# SimulatorT2InterfaceRevE.net
KiCad netlist of a schematic drawn in EAGLE
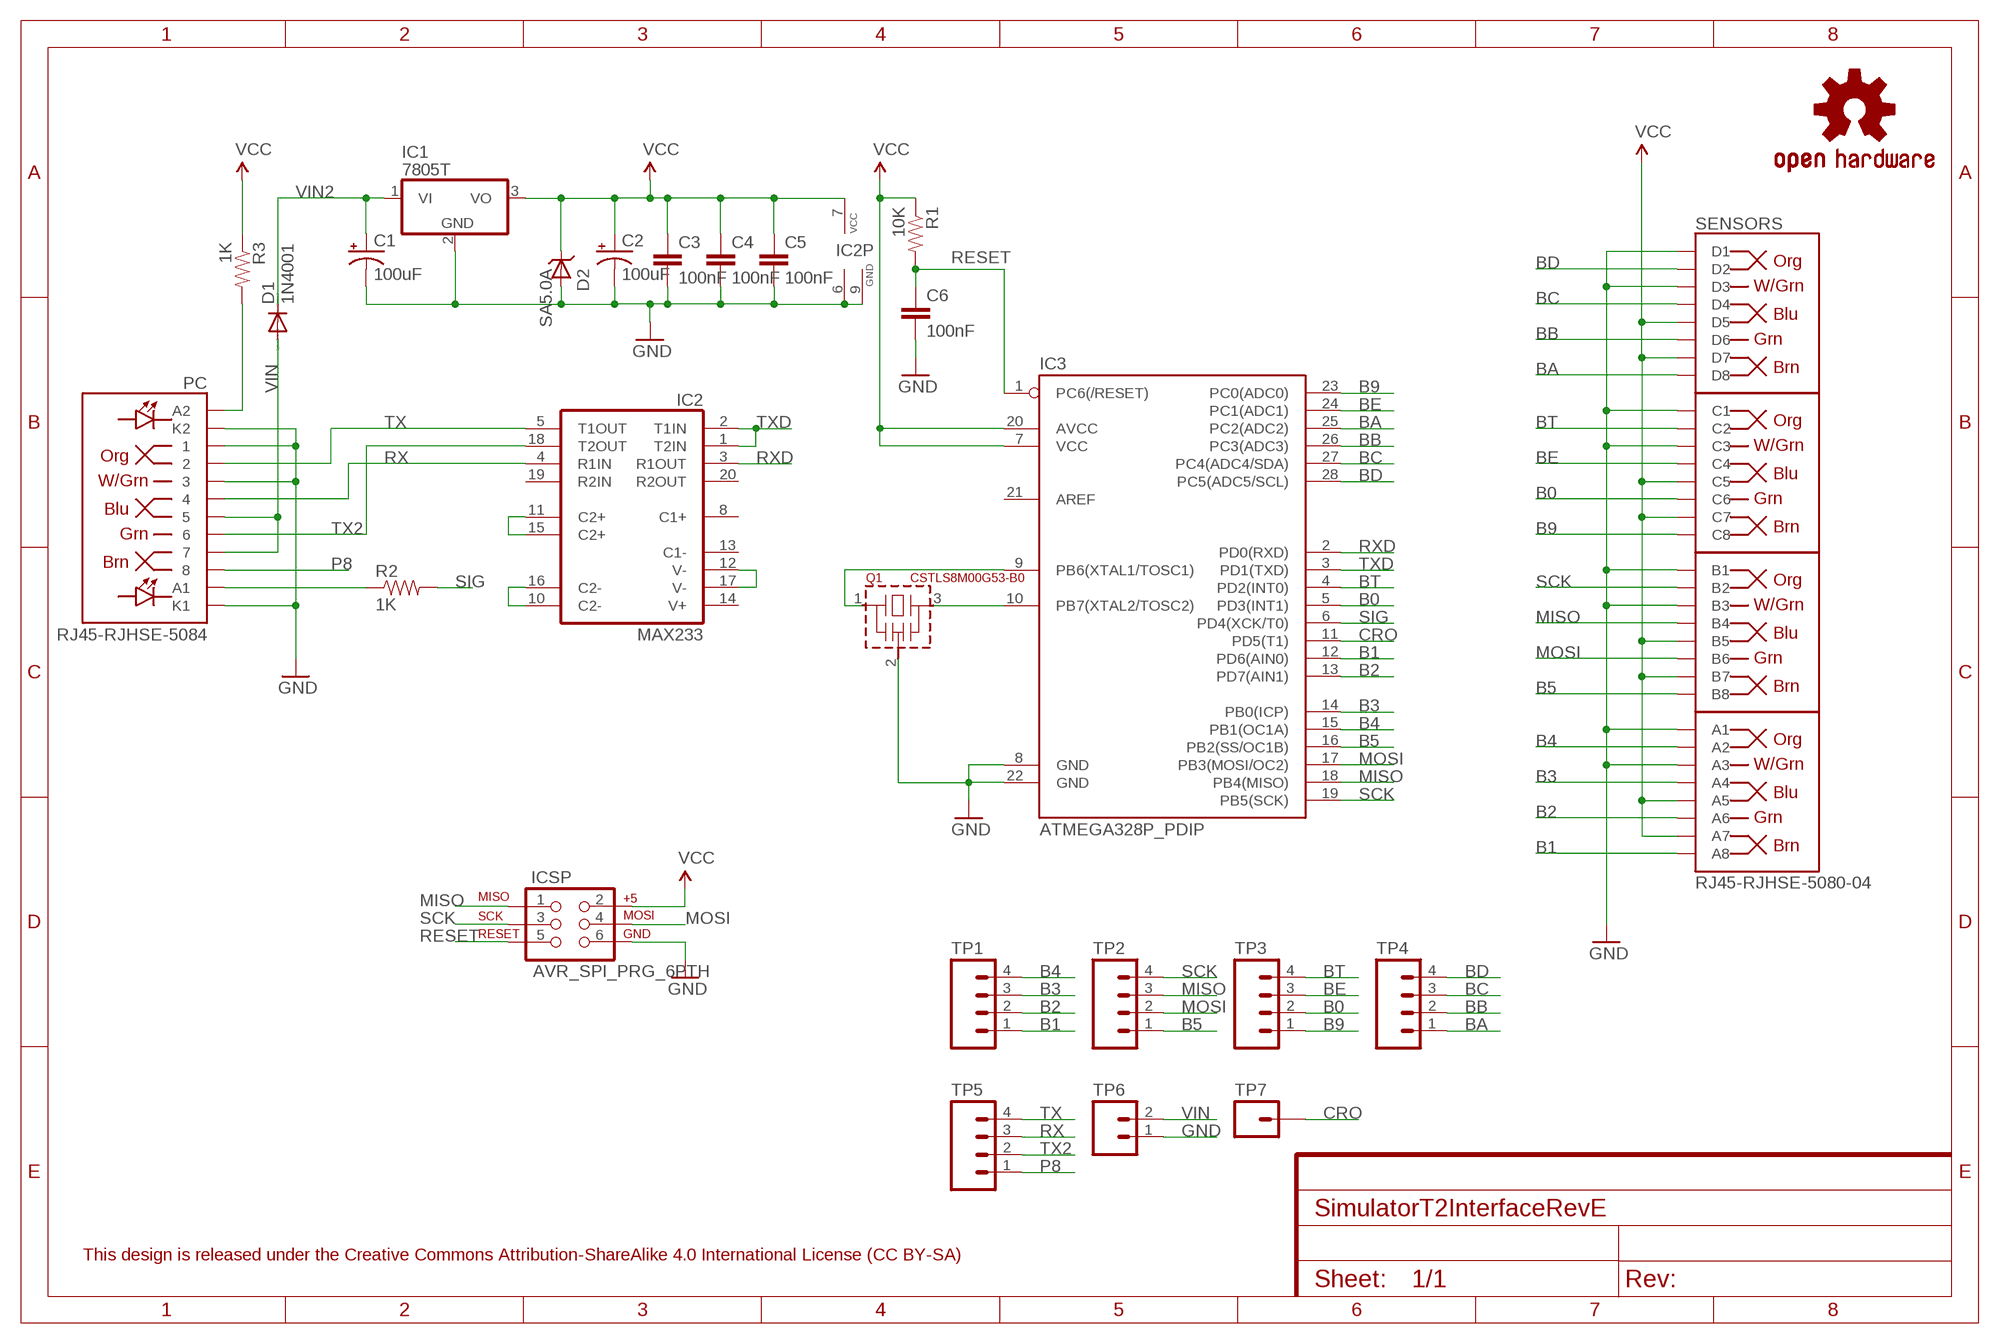
[diagram p0: schematic, sheet 1]

(export (version "E")
  (design (tool "Eeschema 10.0.6"))
  (components
    (comp (ref "C1")
      (value "100uF")
      (footprint "eagle-import:CPOL-RADIAL-100UF-25V")
      (libsource (lib "eagle-import") (part "CAP_POLPTH1"))
    )
    (comp (ref "C2")
      (value "100uF")
      (footprint "eagle-import:CPOL-RADIAL-100UF-25V")
      (libsource (lib "eagle-import") (part "CAP_POLPTH1"))
    )
    (comp (ref "C3")
      (value "100nF")
      (footprint "eagle-import:CAP-PTH-SMALL")
      (libsource (lib "eagle-import") (part "CAPPTH"))
    )
    (comp (ref "C4")
      (value "100nF")
      (footprint "eagle-import:CAP-PTH-SMALL")
      (libsource (lib "eagle-import") (part "CAPPTH"))
    )
    (comp (ref "C5")
      (value "100nF")
      (footprint "eagle-import:CAP-PTH-SMALL")
      (libsource (lib "eagle-import") (part "CAPPTH"))
    )
    (comp (ref "C6")
      (value "100nF")
      (footprint "eagle-import:CAP-PTH-SMALL")
      (libsource (lib "eagle-import") (part "CAPPTH"))
    )
    (comp (ref "D1")
      (value "1N4001")
      (footprint "eagle-import:DO41_DIODE")
      (libsource (lib "eagle-import") (part "1N4001"))
    )
    (comp (ref "D2")
      (value "SA5.0A")
      (footprint "eagle-import:DO41_TVS_UNI")
      (libsource (lib "eagle-import") (part "SA5.0A"))
    )
    (comp (ref "IC1")
      (value "7805T")
      (footprint "eagle-import:TO220H+TSR")
      (libsource (lib "eagle-import") (part "7805T"))
    )
    (comp (ref "IC2")
      (value "MAX233")
      (footprint "eagle-import:DIL20")
      (fields (field (name "MPN") "MAX233ACPP+G36"))
      (libsource (lib "eagle-import") (part "MAX233"))
    )
    (comp (ref "IC3")
      (value "ATMEGA328P_PDIP")
      (footprint "eagle-import:DIL28-3")
      (libsource (lib "eagle-import") (part "ATMEGA328P_PDIP"))
    )
    (comp (ref "ICSP")
      (value "AVR_SPI_PRG_6PTH")
      (footprint "eagle-import:2X3")
      (libsource (lib "eagle-import") (part "AVR_SPI_PRG_6PTH"))
    )
    (comp (ref "LOGO1")
      (value "OSHW-LOGOS")
      (footprint "eagle-import:OSHW-LOGO-S")
      (libsource (lib "eagle-import") (part "OSHW-LOGOS"))
    )
    (comp (ref "PC")
      (value "RJ45-RJHSE-5084")
      (footprint "eagle-import:RJ45-RJHSE-5084")
      (libsource (lib "eagle-import") (part "RJ45-RJHSE-5084"))
    )
    (comp (ref "Q1")
      (value "CSTLS8M00G53-B0")
      (footprint "eagle-import:CSTLS_G9")
      (libsource (lib "eagle-import") (part "murata-resonators_CSTLS_G"))
    )
    (comp (ref "R1")
      (value "10K")
      (footprint "eagle-import:AXIAL-0.4")
      (libsource (lib "eagle-import") (part "RESISTORPTH-1/4W"))
    )
    (comp (ref "R2")
      (value "1K")
      (footprint "eagle-import:AXIAL-0.4")
      (libsource (lib "eagle-import") (part "RESISTORPTH-1/4W"))
    )
    (comp (ref "R3")
      (value "1K")
      (footprint "eagle-import:AXIAL-0.4")
      (libsource (lib "eagle-import") (part "RESISTORPTH-1/4W"))
    )
    (comp (ref "SENSORS")
      (value "RJ45-RJHSE-5080-04")
      (footprint "eagle-import:RJ45-RJHSE-5080-04")
      (libsource (lib "eagle-import") (part "RJ45-RJHSE-5080-04"))
    )
    (comp (ref "TP1")
      (value "M04PTH")
      (footprint "eagle-import:1X04")
      (libsource (lib "eagle-import") (part "M04PTH"))
    )
    (comp (ref "TP2")
      (value "M04PTH")
      (footprint "eagle-import:1X04")
      (libsource (lib "eagle-import") (part "M04PTH"))
    )
    (comp (ref "TP3")
      (value "M04PTH")
      (footprint "eagle-import:1X04")
      (libsource (lib "eagle-import") (part "M04PTH"))
    )
    (comp (ref "TP4")
      (value "M04PTH")
      (footprint "eagle-import:1X04")
      (libsource (lib "eagle-import") (part "M04PTH"))
    )
    (comp (ref "TP5")
      (value "M04PTH")
      (footprint "eagle-import:1X04")
      (libsource (lib "eagle-import") (part "M04PTH"))
    )
    (comp (ref "TP6")
      (value "M02PTH")
      (footprint "eagle-import:1X02")
      (libsource (lib "eagle-import") (part "M02PTH"))
    )
    (comp (ref "TP7")
      (value "M01PTH")
      (footprint "eagle-import:1X01")
      (libsource (lib "eagle-import") (part "M01PTH"))
    )
  )
  (nets
    (net (code "1") (name "/B0") (class "Default")
      (node (ref "IC3") (pin "5") (pinfunction "PD3(INT1)_5") (pintype "bidirectional"))
      (node (ref "SENSORS") (pin "C6") (pinfunction "C6_C6") (pintype "bidirectional"))
      (node (ref "TP3") (pin "2") (pinfunction "2_2") (pintype "passive"))
    )
    (net (code "2") (name "/B1") (class "Default")
      (node (ref "IC3") (pin "12") (pinfunction "PD6(AIN0)_12") (pintype "bidirectional"))
      (node (ref "SENSORS") (pin "A8") (pinfunction "A8_A8") (pintype "bidirectional"))
      (node (ref "TP1") (pin "1") (pinfunction "1_1") (pintype "passive"))
    )
    (net (code "3") (name "/B2") (class "Default")
      (node (ref "IC3") (pin "13") (pinfunction "PD7(AIN1)_13") (pintype "bidirectional"))
      (node (ref "SENSORS") (pin "A6") (pinfunction "A6_A6") (pintype "bidirectional"))
      (node (ref "TP1") (pin "2") (pinfunction "2_2") (pintype "passive"))
    )
    (net (code "4") (name "/B3") (class "Default")
      (node (ref "IC3") (pin "14") (pinfunction "PB0(ICP)_14") (pintype "bidirectional"))
      (node (ref "SENSORS") (pin "A4") (pinfunction "A4_A4") (pintype "bidirectional"))
      (node (ref "TP1") (pin "3") (pinfunction "3_3") (pintype "passive"))
    )
    (net (code "5") (name "/B4") (class "Default")
      (node (ref "IC3") (pin "15") (pinfunction "PB1(OC1A)_15") (pintype "bidirectional"))
      (node (ref "SENSORS") (pin "A2") (pinfunction "A2_A2") (pintype "bidirectional"))
      (node (ref "TP1") (pin "4") (pinfunction "4_4") (pintype "passive"))
    )
    (net (code "6") (name "/B5") (class "Default")
      (node (ref "IC3") (pin "16") (pinfunction "PB2(SS/OC1B)_16") (pintype "bidirectional"))
      (node (ref "SENSORS") (pin "B8") (pinfunction "B8_B8") (pintype "bidirectional"))
      (node (ref "TP2") (pin "1") (pinfunction "1_1") (pintype "passive"))
    )
    (net (code "7") (name "/B9") (class "Default")
      (node (ref "IC3") (pin "23") (pinfunction "PC0(ADC0)_23") (pintype "bidirectional"))
      (node (ref "SENSORS") (pin "C8") (pinfunction "C8_C8") (pintype "bidirectional"))
      (node (ref "TP3") (pin "1") (pinfunction "1_1") (pintype "passive"))
    )
    (net (code "8") (name "/BA") (class "Default")
      (node (ref "IC3") (pin "25") (pinfunction "PC2(ADC2)_25") (pintype "bidirectional"))
      (node (ref "SENSORS") (pin "D8") (pinfunction "D8_D8") (pintype "bidirectional"))
      (node (ref "TP4") (pin "1") (pinfunction "1_1") (pintype "passive"))
    )
    (net (code "9") (name "/BB") (class "Default")
      (node (ref "IC3") (pin "26") (pinfunction "PC3(ADC3)_26") (pintype "bidirectional"))
      (node (ref "SENSORS") (pin "D6") (pinfunction "D6_D6") (pintype "bidirectional"))
      (node (ref "TP4") (pin "2") (pinfunction "2_2") (pintype "passive"))
    )
    (net (code "10") (name "/BC") (class "Default")
      (node (ref "IC3") (pin "27") (pinfunction "PC4(ADC4/SDA)_27") (pintype "bidirectional"))
      (node (ref "SENSORS") (pin "D4") (pinfunction "D4_D4") (pintype "bidirectional"))
      (node (ref "TP4") (pin "3") (pinfunction "3_3") (pintype "passive"))
    )
    (net (code "11") (name "/BD") (class "Default")
      (node (ref "IC3") (pin "28") (pinfunction "PC5(ADC5/SCL)_28") (pintype "bidirectional"))
      (node (ref "SENSORS") (pin "D2") (pinfunction "D2_D2") (pintype "bidirectional"))
      (node (ref "TP4") (pin "4") (pinfunction "4_4") (pintype "passive"))
    )
    (net (code "12") (name "/BE") (class "Default")
      (node (ref "IC3") (pin "24") (pinfunction "PC1(ADC1)_24") (pintype "bidirectional"))
      (node (ref "SENSORS") (pin "C4") (pinfunction "C4_C4") (pintype "bidirectional"))
      (node (ref "TP3") (pin "3") (pinfunction "3_3") (pintype "passive"))
    )
    (net (code "13") (name "/BT") (class "Default")
      (node (ref "IC3") (pin "4") (pinfunction "PD2(INT0)_4") (pintype "bidirectional"))
      (node (ref "SENSORS") (pin "C2") (pinfunction "C2_C2") (pintype "bidirectional"))
      (node (ref "TP3") (pin "4") (pinfunction "4_4") (pintype "passive"))
    )
    (net (code "14") (name "/CRO") (class "Default")
      (node (ref "IC3") (pin "11") (pinfunction "PD5(T1)_11") (pintype "bidirectional"))
      (node (ref "TP7") (pin "1") (pinfunction "1_1") (pintype "passive"))
    )
    (net (code "15") (name "/MISO") (class "Default")
      (node (ref "IC3") (pin "18") (pinfunction "PB4(MISO)_18") (pintype "bidirectional"))
      (node (ref "ICSP") (pin "1") (pinfunction "1_1") (pintype "passive"))
      (node (ref "SENSORS") (pin "B4") (pinfunction "B4_B4") (pintype "bidirectional"))
      (node (ref "TP2") (pin "3") (pinfunction "3_3") (pintype "passive"))
    )
    (net (code "16") (name "/MOSI") (class "Default")
      (node (ref "IC3") (pin "17") (pinfunction "PB3(MOSI/OC2)_17") (pintype "bidirectional"))
      (node (ref "ICSP") (pin "4") (pinfunction "4_4") (pintype "passive"))
      (node (ref "SENSORS") (pin "B6") (pinfunction "B6_B6") (pintype "bidirectional"))
      (node (ref "TP2") (pin "2") (pinfunction "2_2") (pintype "passive"))
    )
    (net (code "17") (name "/P8") (class "Default")
      (node (ref "PC") (pin "8") (pinfunction "8_8") (pintype "bidirectional"))
      (node (ref "TP5") (pin "1") (pinfunction "1_1") (pintype "passive"))
    )
    (net (code "18") (name "/RESET") (class "Default")
      (node (ref "C6") (pin "1") (pinfunction "1_1") (pintype "passive"))
      (node (ref "IC3") (pin "1") (pinfunction "PC6(/RESET)_1") (pintype "bidirectional"))
      (node (ref "ICSP") (pin "5") (pinfunction "5_5") (pintype "passive"))
      (node (ref "R1") (pin "P$2") (pinfunction "2_P$2") (pintype "passive"))
    )
    (net (code "19") (name "/RX") (class "Default")
      (node (ref "IC2") (pin "4") (pinfunction "R1IN_4") (pintype "input"))
      (node (ref "PC") (pin "4") (pinfunction "4_4") (pintype "bidirectional"))
      (node (ref "TP5") (pin "3") (pinfunction "3_3") (pintype "passive"))
    )
    (net (code "20") (name "/RXD") (class "Default")
      (node (ref "IC2") (pin "3") (pinfunction "R1OUT_3") (pintype "output"))
      (node (ref "IC3") (pin "2") (pinfunction "PD0(RXD)_2") (pintype "bidirectional"))
    )
    (net (code "21") (name "/SCK") (class "Default")
      (node (ref "IC3") (pin "19") (pinfunction "PB5(SCK)_19") (pintype "bidirectional"))
      (node (ref "ICSP") (pin "3") (pinfunction "3_3") (pintype "passive"))
      (node (ref "SENSORS") (pin "B2") (pinfunction "B2_B2") (pintype "bidirectional"))
      (node (ref "TP2") (pin "4") (pinfunction "4_4") (pintype "passive"))
    )
    (net (code "22") (name "/SIG") (class "Default")
      (node (ref "IC3") (pin "6") (pinfunction "PD4(XCK/T0)_6") (pintype "bidirectional"))
      (node (ref "R2") (pin "P$2") (pinfunction "2_P$2") (pintype "passive"))
    )
    (net (code "23") (name "/TX") (class "Default")
      (node (ref "IC2") (pin "5") (pinfunction "T1OUT_5") (pintype "output"))
      (node (ref "PC") (pin "2") (pinfunction "2_2") (pintype "bidirectional"))
      (node (ref "TP5") (pin "4") (pinfunction "4_4") (pintype "passive"))
    )
    (net (code "24") (name "/TX2") (class "Default")
      (node (ref "IC2") (pin "18") (pinfunction "T2OUT_18") (pintype "output"))
      (node (ref "PC") (pin "6") (pinfunction "6_6") (pintype "bidirectional"))
      (node (ref "TP5") (pin "2") (pinfunction "2_2") (pintype "passive"))
    )
    (net (code "25") (name "/TXD") (class "Default")
      (node (ref "IC2") (pin "1") (pinfunction "T2IN_1") (pintype "input"))
      (node (ref "IC2") (pin "2") (pinfunction "T1IN_2") (pintype "input"))
      (node (ref "IC3") (pin "3") (pinfunction "PD1(TXD)_3") (pintype "bidirectional"))
    )
    (net (code "26") (name "/VIN") (class "Default")
      (node (ref "D1") (pin "A") (pinfunction "A_A") (pintype "passive"))
      (node (ref "PC") (pin "5") (pinfunction "5_5") (pintype "bidirectional"))
      (node (ref "PC") (pin "7") (pinfunction "7_7") (pintype "bidirectional"))
      (node (ref "TP6") (pin "2") (pinfunction "2_2") (pintype "passive"))
    )
    (net (code "27") (name "/VIN2") (class "Default")
      (node (ref "C1") (pin "1") (pinfunction "+_1") (pintype "passive"))
      (node (ref "D1") (pin "C") (pinfunction "C_C") (pintype "passive"))
      (node (ref "IC1") (pin "1") (pinfunction "VI_1") (pintype "input"))
    )
    (net (code "28") (name "GND") (class "Default")
      (node (ref "C1") (pin "2") (pinfunction "-_2") (pintype "passive"))
      (node (ref "C2") (pin "2") (pinfunction "-_2") (pintype "passive"))
      (node (ref "C3") (pin "2") (pinfunction "2_2") (pintype "passive"))
      (node (ref "C4") (pin "2") (pinfunction "2_2") (pintype "passive"))
      (node (ref "C5") (pin "2") (pinfunction "2_2") (pintype "passive"))
      (node (ref "C6") (pin "2") (pinfunction "2_2") (pintype "passive"))
      (node (ref "D2") (pin "ANODE") (pinfunction "ANODE_ANODE") (pintype "passive"))
      (node (ref "IC1") (pin "2") (pinfunction "GND_2") (pintype "passive"))
      (node (ref "IC2") (pin "6") (pinfunction "GND_6") (pintype "power_in"))
      (node (ref "IC2") (pin "9") (pinfunction "GND_9") (pintype "power_in"))
      (node (ref "IC3") (pin "22") (pinfunction "GND_22") (pintype "bidirectional"))
      (node (ref "IC3") (pin "8") (pinfunction "GND_8") (pintype "bidirectional"))
      (node (ref "ICSP") (pin "6") (pinfunction "6_6") (pintype "passive"))
      (node (ref "PC") (pin "1") (pinfunction "1_1") (pintype "bidirectional"))
      (node (ref "PC") (pin "3") (pinfunction "3_3") (pintype "bidirectional"))
      (node (ref "PC") (pin "K1") (pinfunction "K1_K1") (pintype "passive"))
      (node (ref "PC") (pin "K2") (pinfunction "K2_K2") (pintype "passive"))
      (node (ref "Q1") (pin "2") (pinfunction "GND_2") (pintype "power_in"))
      (node (ref "SENSORS") (pin "A1") (pinfunction "A1_A1") (pintype "bidirectional"))
      (node (ref "SENSORS") (pin "A3") (pinfunction "A3_A3") (pintype "bidirectional"))
      (node (ref "SENSORS") (pin "B1") (pinfunction "B1_B1") (pintype "bidirectional"))
      (node (ref "SENSORS") (pin "B3") (pinfunction "B3_B3") (pintype "bidirectional"))
      (node (ref "SENSORS") (pin "C1") (pinfunction "C1_C1") (pintype "bidirectional"))
      (node (ref "SENSORS") (pin "C3") (pinfunction "C3_C3") (pintype "bidirectional"))
      (node (ref "SENSORS") (pin "D1") (pinfunction "D1_D1") (pintype "bidirectional"))
      (node (ref "SENSORS") (pin "D3") (pinfunction "D3_D3") (pintype "bidirectional"))
      (node (ref "TP6") (pin "1") (pinfunction "1_1") (pintype "passive"))
    )
    (net (code "29") (name "Net-(IC2A-C2+-Pad11)") (class "Default")
      (node (ref "IC2") (pin "11") (pinfunction "C2+_11") (pintype "bidirectional"))
      (node (ref "IC2") (pin "15") (pinfunction "C2+_15") (pintype "bidirectional"))
    )
    (net (code "30") (name "Net-(IC2A-C2--Pad10)") (class "Default")
      (node (ref "IC2") (pin "10") (pinfunction "C2-_10") (pintype "bidirectional"))
      (node (ref "IC2") (pin "16") (pinfunction "C2-_16") (pintype "bidirectional"))
    )
    (net (code "31") (name "Net-(IC2A-V--Pad12)") (class "Default")
      (node (ref "IC2") (pin "12") (pinfunction "V-_12") (pintype "bidirectional"))
      (node (ref "IC2") (pin "17") (pinfunction "V-_17") (pintype "bidirectional"))
    )
    (net (code "32") (name "Net-(IC3-PB6(XTAL1{slash}TOSC1))") (class "Default")
      (node (ref "IC3") (pin "9") (pinfunction "PB6(XTAL1/TOSC1)_9") (pintype "bidirectional"))
      (node (ref "Q1") (pin "1") (pinfunction "1_1") (pintype "output"))
    )
    (net (code "33") (name "Net-(IC3-PB7(XTAL2{slash}TOSC2))") (class "Default")
      (node (ref "IC3") (pin "10") (pinfunction "PB7(XTAL2/TOSC2)_10") (pintype "bidirectional"))
      (node (ref "Q1") (pin "3") (pinfunction "3_3") (pintype "input"))
    )
    (net (code "34") (name "Net-(R2-1)") (class "Default")
      (node (ref "PC") (pin "A1") (pinfunction "A1_A1") (pintype "passive"))
      (node (ref "R2") (pin "P$1") (pinfunction "1_P$1") (pintype "passive"))
    )
    (net (code "35") (name "Net-(R3-2)") (class "Default")
      (node (ref "PC") (pin "A2") (pinfunction "A2_A2") (pintype "passive"))
      (node (ref "R3") (pin "P$2") (pinfunction "2_P$2") (pintype "passive"))
    )
    (net (code "36") (name "VCC") (class "Default")
      (node (ref "C2") (pin "1") (pinfunction "+_1") (pintype "passive"))
      (node (ref "C3") (pin "1") (pinfunction "1_1") (pintype "passive"))
      (node (ref "C4") (pin "1") (pinfunction "1_1") (pintype "passive"))
      (node (ref "C5") (pin "1") (pinfunction "1_1") (pintype "passive"))
      (node (ref "D2") (pin "CATHODE") (pinfunction "CATHODE_CATHODE") (pintype "passive"))
      (node (ref "IC1") (pin "3") (pinfunction "VO_3") (pintype "passive"))
      (node (ref "IC2") (pin "7") (pinfunction "VCC_7") (pintype "power_in"))
      (node (ref "IC3") (pin "20") (pinfunction "AVCC_20") (pintype "bidirectional"))
      (node (ref "IC3") (pin "7") (pinfunction "VCC_7") (pintype "bidirectional"))
      (node (ref "ICSP") (pin "2") (pinfunction "2_2") (pintype "passive"))
      (node (ref "R1") (pin "P$1") (pinfunction "1_P$1") (pintype "passive"))
      (node (ref "R3") (pin "P$1") (pinfunction "1_P$1") (pintype "passive"))
      (node (ref "SENSORS") (pin "A5") (pinfunction "A5_A5") (pintype "bidirectional"))
      (node (ref "SENSORS") (pin "A7") (pinfunction "A7_A7") (pintype "bidirectional"))
      (node (ref "SENSORS") (pin "B5") (pinfunction "B5_B5") (pintype "bidirectional"))
      (node (ref "SENSORS") (pin "B7") (pinfunction "B7_B7") (pintype "bidirectional"))
      (node (ref "SENSORS") (pin "C5") (pinfunction "C5_C5") (pintype "bidirectional"))
      (node (ref "SENSORS") (pin "C7") (pinfunction "C7_C7") (pintype "bidirectional"))
      (node (ref "SENSORS") (pin "D5") (pinfunction "D5_D5") (pintype "bidirectional"))
      (node (ref "SENSORS") (pin "D7") (pinfunction "D7_D7") (pintype "bidirectional"))
    )
    (net (code "37") (name "unconnected-(IC2A-C1+-Pad8)") (class "Default")
      (node (ref "IC2") (pin "8") (pinfunction "C1+_8") (pintype "bidirectional"))
    )
    (net (code "38") (name "unconnected-(IC2A-C1--Pad13)") (class "Default")
      (node (ref "IC2") (pin "13") (pinfunction "C1-_13") (pintype "bidirectional"))
    )
    (net (code "39") (name "unconnected-(IC2A-R2IN-Pad19)") (class "Default")
      (node (ref "IC2") (pin "19") (pinfunction "R2IN_19") (pintype "input"))
    )
    (net (code "40") (name "unconnected-(IC2A-R2OUT-Pad20)") (class "Default")
      (node (ref "IC2") (pin "20") (pinfunction "R2OUT_20") (pintype "output"))
    )
    (net (code "41") (name "unconnected-(IC2A-V+-Pad14)") (class "Default")
      (node (ref "IC2") (pin "14") (pinfunction "V+_14") (pintype "bidirectional"))
    )
    (net (code "42") (name "unconnected-(IC3-AREF-Pad21)") (class "Default")
      (node (ref "IC3") (pin "21") (pinfunction "AREF_21") (pintype "bidirectional"))
    )
  )
)
